# circuitdraft.net
KiCad netlist of a schematic drawn in EAGLE
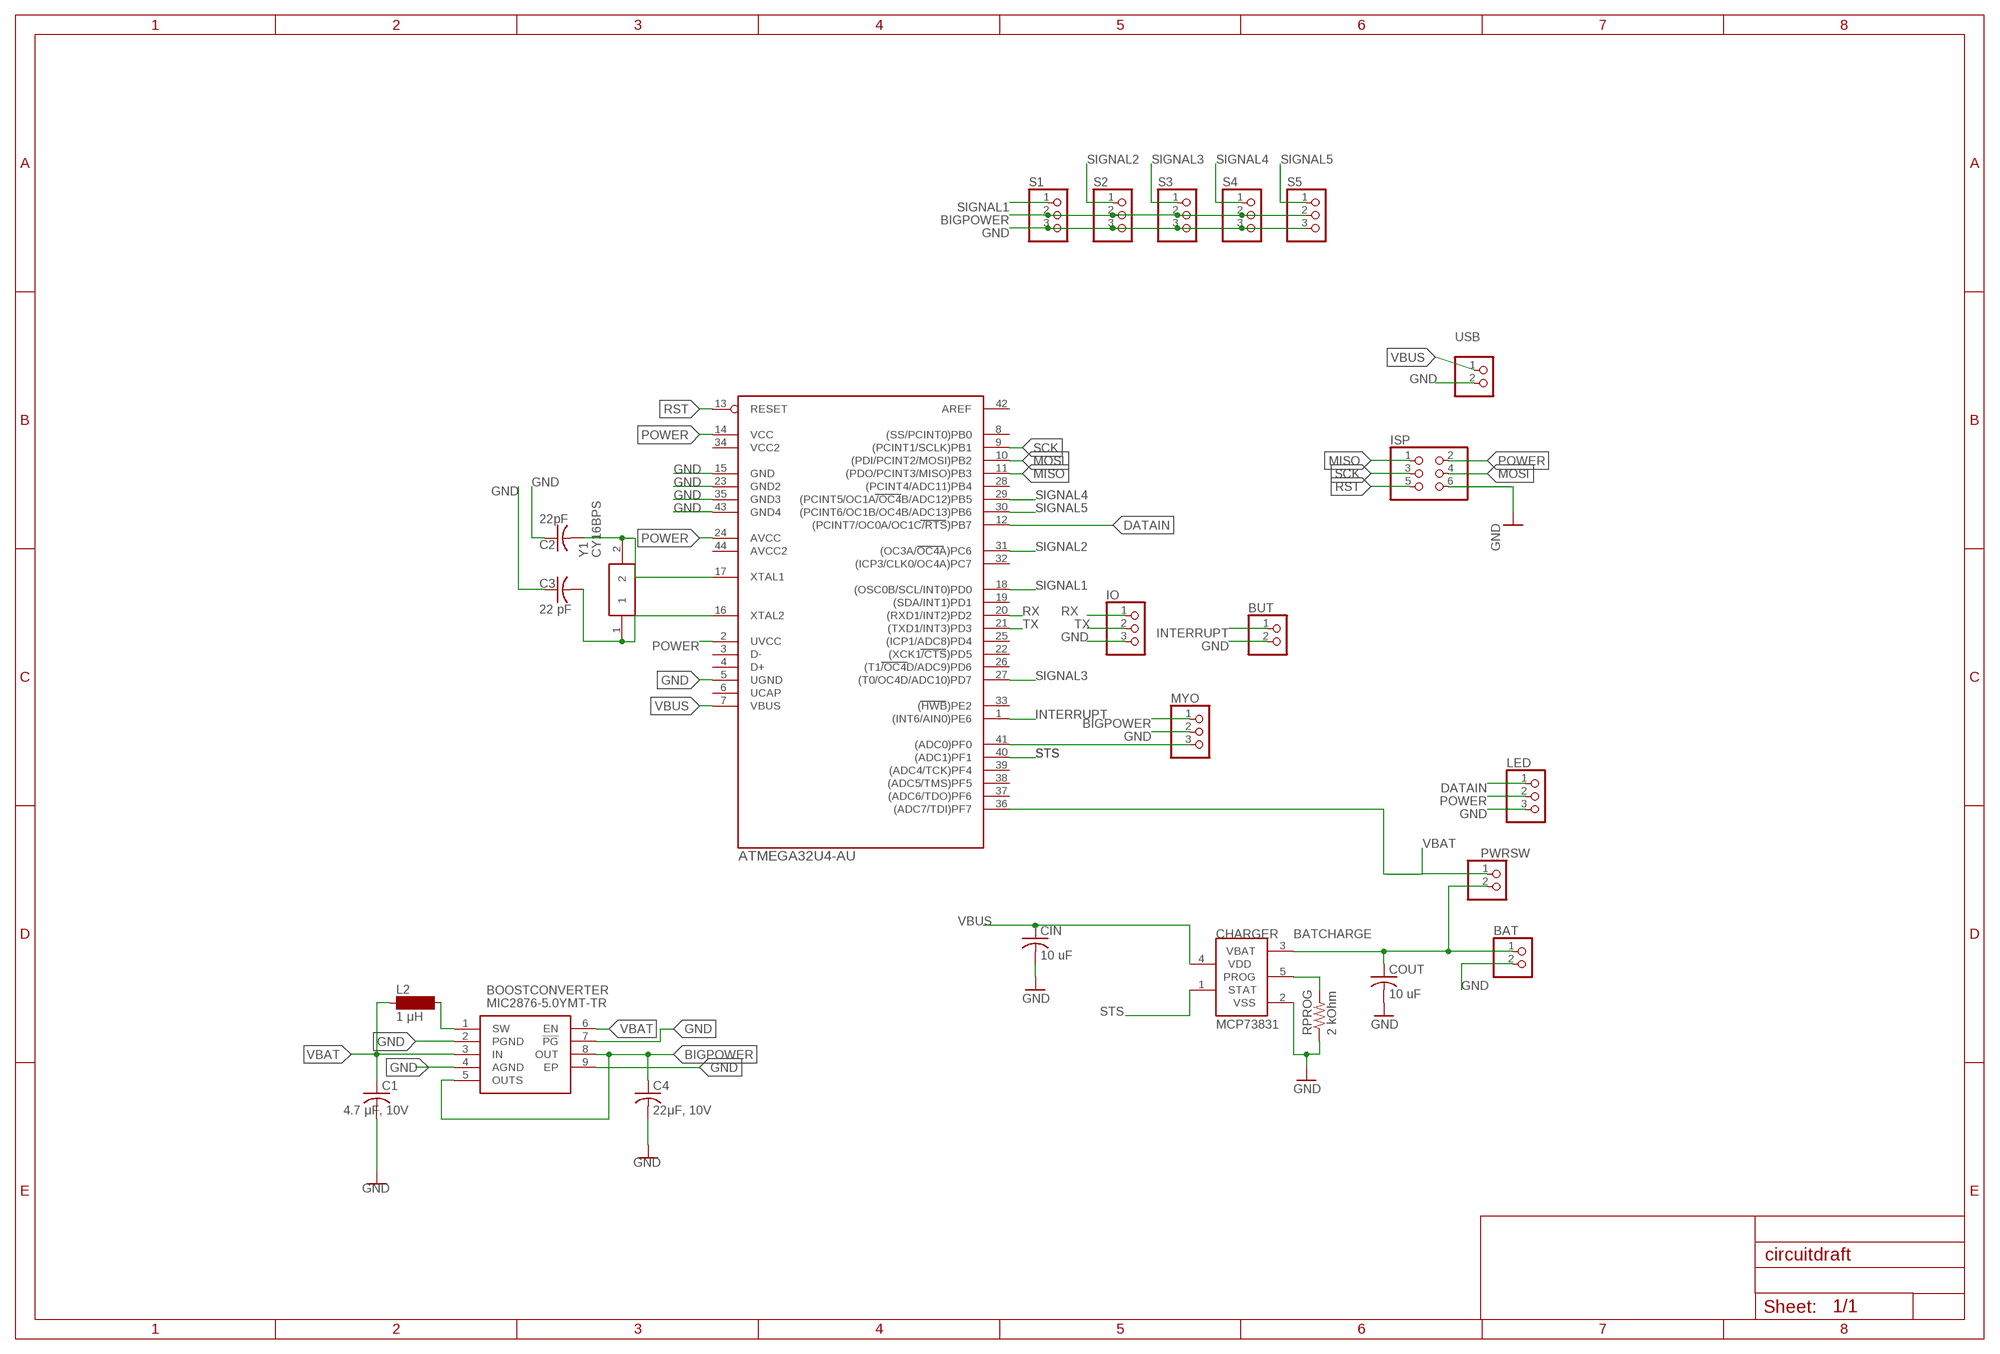
[diagram p0: schematic, sheet 1]

(export (version "E")
  (design (tool "Eeschema 10.0.6"))
  (components
    (comp (ref "BAT")
      (value "PINHD-1X2")
      (footprint "eagle-import:1X02")
      (libsource (lib "eagle-import") (part "PINHD-1X2"))
    )
    (comp (ref "BOOSTCONVERTER")
      (value "MIC2876-5.0YMT-TR")
      (footprint "eagle-import:MIC287650YMTTR")
      (fields (field (name "MOUSER_PART_NUMBER") "998-MIC2876-50YMTTR"))
      (libsource (lib "eagle-import") (part "MIC2876-5.0YMT-TR"))
    )
    (comp (ref "BUT")
      (value "PINHD-1X2")
      (footprint "eagle-import:1X02")
      (libsource (lib "eagle-import") (part "PINHD-1X2"))
    )
    (comp (ref "C1")
      (value "4.7 μF, 10V")
      (footprint "eagle-import:C0603")
      (libsource (lib "eagle-import") (part "C-USC0603"))
    )
    (comp (ref "C2")
      (value "22pF")
      (footprint "eagle-import:C025-024X044")
      (libsource (lib "eagle-import") (part "C-US025-024X044"))
    )
    (comp (ref "C3")
      (value "22 pF")
      (footprint "eagle-import:C025-024X044")
      (libsource (lib "eagle-import") (part "C-US025-024X044"))
    )
    (comp (ref "C4")
      (value "22μF, 10V")
      (footprint "eagle-import:C0603")
      (libsource (lib "eagle-import") (part "C-USC0603"))
    )
    (comp (ref "CHARGER")
      (value "MCP73831")
      (footprint "eagle-import:SOT23-5L")
      (libsource (lib "eagle-import") (part "MCP73831"))
    )
    (comp (ref "CIN")
      (value "10 uF")
      (footprint "eagle-import:C0603")
      (libsource (lib "eagle-import") (part "C-USC0603"))
    )
    (comp (ref "COUT")
      (value "10 uF")
      (footprint "eagle-import:C0603")
      (libsource (lib "eagle-import") (part "C-USC0603"))
    )
    (comp (ref "IO")
      (value "PINHD-1X3")
      (footprint "eagle-import:1X03")
      (libsource (lib "eagle-import") (part "PINHD-1X3"))
    )
    (comp (ref "ISP")
      (value "PINHD-2X3")
      (footprint "eagle-import:2X03")
      (libsource (lib "eagle-import") (part "PINHD-2X3"))
    )
    (comp (ref "L2")
      (value "1 μH")
      (footprint "eagle-import:SD75")
      (libsource (lib "eagle-import") (part "SD75"))
    )
    (comp (ref "LED")
      (value "PINHD-1X3")
      (footprint "eagle-import:1X03")
      (libsource (lib "eagle-import") (part "PINHD-1X3"))
    )
    (comp (ref "MYO")
      (value "PINHD-1X3")
      (footprint "eagle-import:1X03")
      (libsource (lib "eagle-import") (part "PINHD-1X3"))
    )
    (comp (ref "PWRSW")
      (value "PINHD-1X2")
      (footprint "eagle-import:1X02")
      (libsource (lib "eagle-import") (part "PINHD-1X2"))
    )
    (comp (ref "RPROG")
      (value "2 kOhm")
      (footprint "eagle-import:R0603")
      (libsource (lib "eagle-import") (part "R-US_R0603"))
    )
    (comp (ref "S1")
      (value "PINHD-1X3")
      (footprint "eagle-import:1X03")
      (libsource (lib "eagle-import") (part "PINHD-1X3"))
    )
    (comp (ref "S2")
      (value "PINHD-1X3")
      (footprint "eagle-import:1X03")
      (libsource (lib "eagle-import") (part "PINHD-1X3"))
    )
    (comp (ref "S3")
      (value "PINHD-1X3")
      (footprint "eagle-import:1X03")
      (libsource (lib "eagle-import") (part "PINHD-1X3"))
    )
    (comp (ref "S4")
      (value "PINHD-1X3")
      (footprint "eagle-import:1X03")
      (libsource (lib "eagle-import") (part "PINHD-1X3"))
    )
    (comp (ref "S5")
      (value "PINHD-1X3")
      (footprint "eagle-import:1X03")
      (libsource (lib "eagle-import") (part "PINHD-1X3"))
    )
    (comp (ref "U$1")
      (value "ATMEGA32U4-AU")
      (footprint "eagle-import:TQFP44")
      (libsource (lib "eagle-import") (part "ATMEGA32U4-AU"))
    )
    (comp (ref "USB")
      (value "PINHD-1X2")
      (footprint "eagle-import:1X02")
      (libsource (lib "eagle-import") (part "PINHD-1X2"))
    )
    (comp (ref "Y1")
      (value "CY16BPS")
      (footprint "eagle-import:CY16BPS")
      (fields (field (name "MOUSER_PART_NUMBER") "549-CY16BPS"))
      (libsource (lib "eagle-import") (part "CY16BPS"))
    )
  )
  (nets
    (net (code "1") (name "/BATCHARGE") (class "Default")
      (node (ref "BAT") (pin "1") (pinfunction "1_1") (pintype "passive"))
      (node (ref "CHARGER") (pin "3") (pinfunction "VBAT_3") (pintype "bidirectional"))
      (node (ref "COUT") (pin "1") (pinfunction "1_1") (pintype "passive"))
      (node (ref "PWRSW") (pin "2") (pinfunction "2_2") (pintype "passive"))
    )
    (net (code "2") (name "/INTERRUPT") (class "Default")
      (node (ref "BUT") (pin "1") (pinfunction "1_1") (pintype "passive"))
      (node (ref "U$1") (pin "1") (pinfunction "(INT6/AIN0)PE6_1") (pintype "bidirectional"))
    )
    (net (code "3") (name "/RX") (class "Default")
      (node (ref "IO") (pin "1") (pinfunction "1_1") (pintype "passive"))
      (node (ref "U$1") (pin "20") (pinfunction "(RXD1/INT2)PD2_20") (pintype "bidirectional"))
    )
    (net (code "4") (name "/SIGNAL1") (class "Default")
      (node (ref "S1") (pin "1") (pinfunction "1_1") (pintype "passive"))
      (node (ref "U$1") (pin "18") (pinfunction "(OSC0B/SCL/INT0)PD0_18") (pintype "bidirectional"))
    )
    (net (code "5") (name "/SIGNAL2") (class "Default")
      (node (ref "S2") (pin "1") (pinfunction "1_1") (pintype "passive"))
      (node (ref "U$1") (pin "31") (pinfunction "(OC3A/OC4A)PC6_31") (pintype "bidirectional"))
    )
    (net (code "6") (name "/SIGNAL3") (class "Default")
      (node (ref "S3") (pin "1") (pinfunction "1_1") (pintype "passive"))
      (node (ref "U$1") (pin "27") (pinfunction "(T0/OC4D/ADC10)PD7_27") (pintype "bidirectional"))
    )
    (net (code "7") (name "/SIGNAL4") (class "Default")
      (node (ref "S4") (pin "1") (pinfunction "1_1") (pintype "passive"))
      (node (ref "U$1") (pin "29") (pinfunction "(PCINT5/OC1A/OC4B/ADC12)PB5_29") (pintype "bidirectional"))
    )
    (net (code "8") (name "/SIGNAL5") (class "Default")
      (node (ref "S5") (pin "1") (pinfunction "1_1") (pintype "passive"))
      (node (ref "U$1") (pin "30") (pinfunction "(PCINT6/OC1B/OC4B/ADC13)PB6_30") (pintype "bidirectional"))
    )
    (net (code "9") (name "/STS") (class "Default")
      (node (ref "CHARGER") (pin "1") (pinfunction "STAT_1") (pintype "bidirectional"))
      (node (ref "U$1") (pin "40") (pinfunction "(ADC1)PF1_40") (pintype "bidirectional"))
    )
    (net (code "10") (name "/TX") (class "Default")
      (node (ref "IO") (pin "2") (pinfunction "2_2") (pintype "passive"))
      (node (ref "U$1") (pin "21") (pinfunction "(TXD1/INT3)PD3_21") (pintype "bidirectional"))
    )
    (net (code "11") (name "BIGPOWER") (class "Default")
      (node (ref "BOOSTCONVERTER") (pin "5") (pinfunction "OUTS_5") (pintype "bidirectional"))
      (node (ref "BOOSTCONVERTER") (pin "8") (pinfunction "OUT_8") (pintype "bidirectional"))
      (node (ref "C4") (pin "1") (pinfunction "1_1") (pintype "passive"))
      (node (ref "MYO") (pin "1") (pinfunction "1_1") (pintype "passive"))
      (node (ref "S1") (pin "2") (pinfunction "2_2") (pintype "passive"))
      (node (ref "S2") (pin "2") (pinfunction "2_2") (pintype "passive"))
      (node (ref "S3") (pin "2") (pinfunction "2_2") (pintype "passive"))
      (node (ref "S4") (pin "2") (pinfunction "2_2") (pintype "passive"))
      (node (ref "S5") (pin "2") (pinfunction "2_2") (pintype "passive"))
    )
    (net (code "12") (name "DATAIN") (class "Default")
      (node (ref "LED") (pin "1") (pinfunction "1_1") (pintype "passive"))
      (node (ref "U$1") (pin "12") (pinfunction "(PCINT7/OC0A/OC1C/RTS)PB7_12") (pintype "bidirectional"))
    )
    (net (code "13") (name "GND") (class "Default")
      (node (ref "BAT") (pin "2") (pinfunction "2_2") (pintype "passive"))
      (node (ref "BOOSTCONVERTER") (pin "2") (pinfunction "PGND_2") (pintype "bidirectional"))
      (node (ref "BOOSTCONVERTER") (pin "4") (pinfunction "AGND_4") (pintype "bidirectional"))
      (node (ref "BOOSTCONVERTER") (pin "7") (pinfunction "~{PG}_7") (pintype "bidirectional"))
      (node (ref "BOOSTCONVERTER") (pin "9") (pinfunction "EP_9") (pintype "bidirectional"))
      (node (ref "BUT") (pin "2") (pinfunction "2_2") (pintype "passive"))
      (node (ref "C1") (pin "2") (pinfunction "2_2") (pintype "passive"))
      (node (ref "C2") (pin "1") (pinfunction "1_1") (pintype "passive"))
      (node (ref "C3") (pin "1") (pinfunction "1_1") (pintype "passive"))
      (node (ref "C4") (pin "2") (pinfunction "2_2") (pintype "passive"))
      (node (ref "CHARGER") (pin "2") (pinfunction "VSS_2") (pintype "bidirectional"))
      (node (ref "CIN") (pin "2") (pinfunction "2_2") (pintype "passive"))
      (node (ref "COUT") (pin "2") (pinfunction "2_2") (pintype "passive"))
      (node (ref "IO") (pin "3") (pinfunction "3_3") (pintype "passive"))
      (node (ref "ISP") (pin "6") (pinfunction "6_6") (pintype "passive"))
      (node (ref "LED") (pin "3") (pinfunction "3_3") (pintype "passive"))
      (node (ref "MYO") (pin "2") (pinfunction "2_2") (pintype "passive"))
      (node (ref "RPROG") (pin "1") (pinfunction "1_1") (pintype "passive"))
      (node (ref "S1") (pin "3") (pinfunction "3_3") (pintype "passive"))
      (node (ref "S2") (pin "3") (pinfunction "3_3") (pintype "passive"))
      (node (ref "S3") (pin "3") (pinfunction "3_3") (pintype "passive"))
      (node (ref "S4") (pin "3") (pinfunction "3_3") (pintype "passive"))
      (node (ref "S5") (pin "3") (pinfunction "3_3") (pintype "passive"))
      (node (ref "U$1") (pin "15") (pinfunction "GND_15") (pintype "bidirectional"))
      (node (ref "U$1") (pin "23") (pinfunction "GND2_23") (pintype "bidirectional"))
      (node (ref "U$1") (pin "35") (pinfunction "GND3_35") (pintype "bidirectional"))
      (node (ref "U$1") (pin "43") (pinfunction "GND4_43") (pintype "bidirectional"))
      (node (ref "U$1") (pin "5") (pinfunction "UGND_5") (pintype "bidirectional"))
      (node (ref "USB") (pin "2") (pinfunction "2_2") (pintype "passive"))
    )
    (net (code "14") (name "MISO") (class "Default")
      (node (ref "ISP") (pin "1") (pinfunction "1_1") (pintype "passive"))
      (node (ref "U$1") (pin "11") (pinfunction "(PDO/PCINT3/MISO)PB3_11") (pintype "bidirectional"))
    )
    (net (code "15") (name "MOSI") (class "Default")
      (node (ref "ISP") (pin "4") (pinfunction "4_4") (pintype "passive"))
      (node (ref "U$1") (pin "10") (pinfunction "(PDI/PCINT2/MOSI)PB2_10") (pintype "bidirectional"))
    )
    (net (code "16") (name "Net-(BOOSTCONVERTER-SW)") (class "Default")
      (node (ref "BOOSTCONVERTER") (pin "1") (pinfunction "SW_1") (pintype "bidirectional"))
      (node (ref "L2") (pin "2") (pinfunction "2_2") (pintype "passive"))
    )
    (net (code "17") (name "Net-(CHARGER-PROG)") (class "Default")
      (node (ref "CHARGER") (pin "5") (pinfunction "PROG_5") (pintype "bidirectional"))
      (node (ref "RPROG") (pin "2") (pinfunction "2_2") (pintype "passive"))
    )
    (net (code "18") (name "Net-(U$1-(ADC0)PF0)") (class "Default")
      (node (ref "MYO") (pin "3") (pinfunction "3_3") (pintype "passive"))
      (node (ref "U$1") (pin "41") (pinfunction "(ADC0)PF0_41") (pintype "bidirectional"))
    )
    (net (code "19") (name "Net-(U$1-XTAL1)") (class "Default")
      (node (ref "C2") (pin "2") (pinfunction "2_2") (pintype "passive"))
      (node (ref "U$1") (pin "17") (pinfunction "XTAL1_17") (pintype "bidirectional"))
      (node (ref "Y1") (pin "2") (pinfunction "2_2") (pintype "bidirectional"))
    )
    (net (code "20") (name "Net-(U$1-XTAL2)") (class "Default")
      (node (ref "C3") (pin "2") (pinfunction "2_2") (pintype "passive"))
      (node (ref "U$1") (pin "16") (pinfunction "XTAL2_16") (pintype "bidirectional"))
      (node (ref "Y1") (pin "1") (pinfunction "1_1") (pintype "bidirectional"))
    )
    (net (code "21") (name "POWER") (class "Default")
      (node (ref "ISP") (pin "2") (pinfunction "2_2") (pintype "passive"))
      (node (ref "LED") (pin "2") (pinfunction "2_2") (pintype "passive"))
      (node (ref "U$1") (pin "14") (pinfunction "VCC_14") (pintype "bidirectional"))
      (node (ref "U$1") (pin "2") (pinfunction "UVCC_2") (pintype "bidirectional"))
      (node (ref "U$1") (pin "24") (pinfunction "AVCC_24") (pintype "bidirectional"))
    )
    (net (code "22") (name "RST") (class "Default")
      (node (ref "ISP") (pin "5") (pinfunction "5_5") (pintype "passive"))
      (node (ref "U$1") (pin "13") (pinfunction "RESET_13") (pintype "bidirectional"))
    )
    (net (code "23") (name "SCK") (class "Default")
      (node (ref "ISP") (pin "3") (pinfunction "3_3") (pintype "passive"))
      (node (ref "U$1") (pin "9") (pinfunction "(PCINT1/SCLK)PB1_9") (pintype "bidirectional"))
    )
    (net (code "24") (name "VBAT") (class "Default")
      (node (ref "BOOSTCONVERTER") (pin "3") (pinfunction "IN_3") (pintype "bidirectional"))
      (node (ref "BOOSTCONVERTER") (pin "6") (pinfunction "EN_6") (pintype "bidirectional"))
      (node (ref "C1") (pin "1") (pinfunction "1_1") (pintype "passive"))
      (node (ref "L2") (pin "1") (pinfunction "1_1") (pintype "passive"))
      (node (ref "PWRSW") (pin "1") (pinfunction "1_1") (pintype "passive"))
      (node (ref "U$1") (pin "36") (pinfunction "(ADC7/TDI)PF7_36") (pintype "bidirectional"))
    )
    (net (code "25") (name "VBUS") (class "Default")
      (node (ref "CHARGER") (pin "4") (pinfunction "VDD_4") (pintype "bidirectional"))
      (node (ref "CIN") (pin "1") (pinfunction "1_1") (pintype "passive"))
      (node (ref "U$1") (pin "7") (pinfunction "VBUS_7") (pintype "bidirectional"))
      (node (ref "USB") (pin "1") (pinfunction "1_1") (pintype "passive"))
    )
    (net (code "26") (name "unconnected-(U$1-(ADC4{slash}TCK)PF4-Pad39)") (class "Default")
      (node (ref "U$1") (pin "39") (pinfunction "(ADC4/TCK)PF4_39") (pintype "bidirectional"))
    )
    (net (code "27") (name "unconnected-(U$1-(ADC5{slash}TMS)PF5-Pad38)") (class "Default")
      (node (ref "U$1") (pin "38") (pinfunction "(ADC5/TMS)PF5_38") (pintype "bidirectional"))
    )
    (net (code "28") (name "unconnected-(U$1-(ADC6{slash}TDO)PF6-Pad37)") (class "Default")
      (node (ref "U$1") (pin "37") (pinfunction "(ADC6/TDO)PF6_37") (pintype "bidirectional"))
    )
    (net (code "29") (name "unconnected-(U$1-(HWB)PE2-Pad33)") (class "Default")
      (node (ref "U$1") (pin "33") (pinfunction "(HWB)PE2_33") (pintype "bidirectional"))
    )
    (net (code "30") (name "unconnected-(U$1-(ICP1{slash}ADC8)PD4-Pad25)") (class "Default")
      (node (ref "U$1") (pin "25") (pinfunction "(ICP1/ADC8)PD4_25") (pintype "bidirectional"))
    )
    (net (code "31") (name "unconnected-(U$1-(ICP3{slash}CLK0{slash}OC4A)PC7-Pad32)") (class "Default")
      (node (ref "U$1") (pin "32") (pinfunction "(ICP3/CLK0/OC4A)PC7_32") (pintype "bidirectional"))
    )
    (net (code "32") (name "unconnected-(U$1-(PCINT4{slash}ADC11)PB4-Pad28)") (class "Default")
      (node (ref "U$1") (pin "28") (pinfunction "(PCINT4/ADC11)PB4_28") (pintype "bidirectional"))
    )
    (net (code "33") (name "unconnected-(U$1-(SDA{slash}INT1)PD1-Pad19)") (class "Default")
      (node (ref "U$1") (pin "19") (pinfunction "(SDA/INT1)PD1_19") (pintype "bidirectional"))
    )
    (net (code "34") (name "unconnected-(U$1-(SS{slash}PCINT0)PB0-Pad8)") (class "Default")
      (node (ref "U$1") (pin "8") (pinfunction "(SS/PCINT0)PB0_8") (pintype "bidirectional"))
    )
    (net (code "35") (name "unconnected-(U$1-(T1{slash}OC4D{slash}ADC9)PD6-Pad26)") (class "Default")
      (node (ref "U$1") (pin "26") (pinfunction "(T1/OC4D/ADC9)PD6_26") (pintype "bidirectional"))
    )
    (net (code "36") (name "unconnected-(U$1-(XCK1{slash}CTS)PD5-Pad22)") (class "Default")
      (node (ref "U$1") (pin "22") (pinfunction "(XCK1/CTS)PD5_22") (pintype "bidirectional"))
    )
    (net (code "37") (name "unconnected-(U$1-AREF-Pad42)") (class "Default")
      (node (ref "U$1") (pin "42") (pinfunction "AREF_42") (pintype "bidirectional"))
    )
    (net (code "38") (name "unconnected-(U$1-AVCC2-Pad44)") (class "Default")
      (node (ref "U$1") (pin "44") (pinfunction "AVCC2_44") (pintype "bidirectional"))
    )
    (net (code "39") (name "unconnected-(U$1-D+-Pad4)") (class "Default")
      (node (ref "U$1") (pin "4") (pinfunction "D+_4") (pintype "bidirectional"))
    )
    (net (code "40") (name "unconnected-(U$1-D--Pad3)") (class "Default")
      (node (ref "U$1") (pin "3") (pinfunction "D-_3") (pintype "bidirectional"))
    )
    (net (code "41") (name "unconnected-(U$1-UCAP-Pad6)") (class "Default")
      (node (ref "U$1") (pin "6") (pinfunction "UCAP_6") (pintype "bidirectional"))
    )
    (net (code "42") (name "unconnected-(U$1-VCC2-Pad34)") (class "Default")
      (node (ref "U$1") (pin "34") (pinfunction "VCC2_34") (pintype "bidirectional"))
    )
  )
)
